# ActuatorController.net
KiCad netlist of a schematic drawn in EAGLE
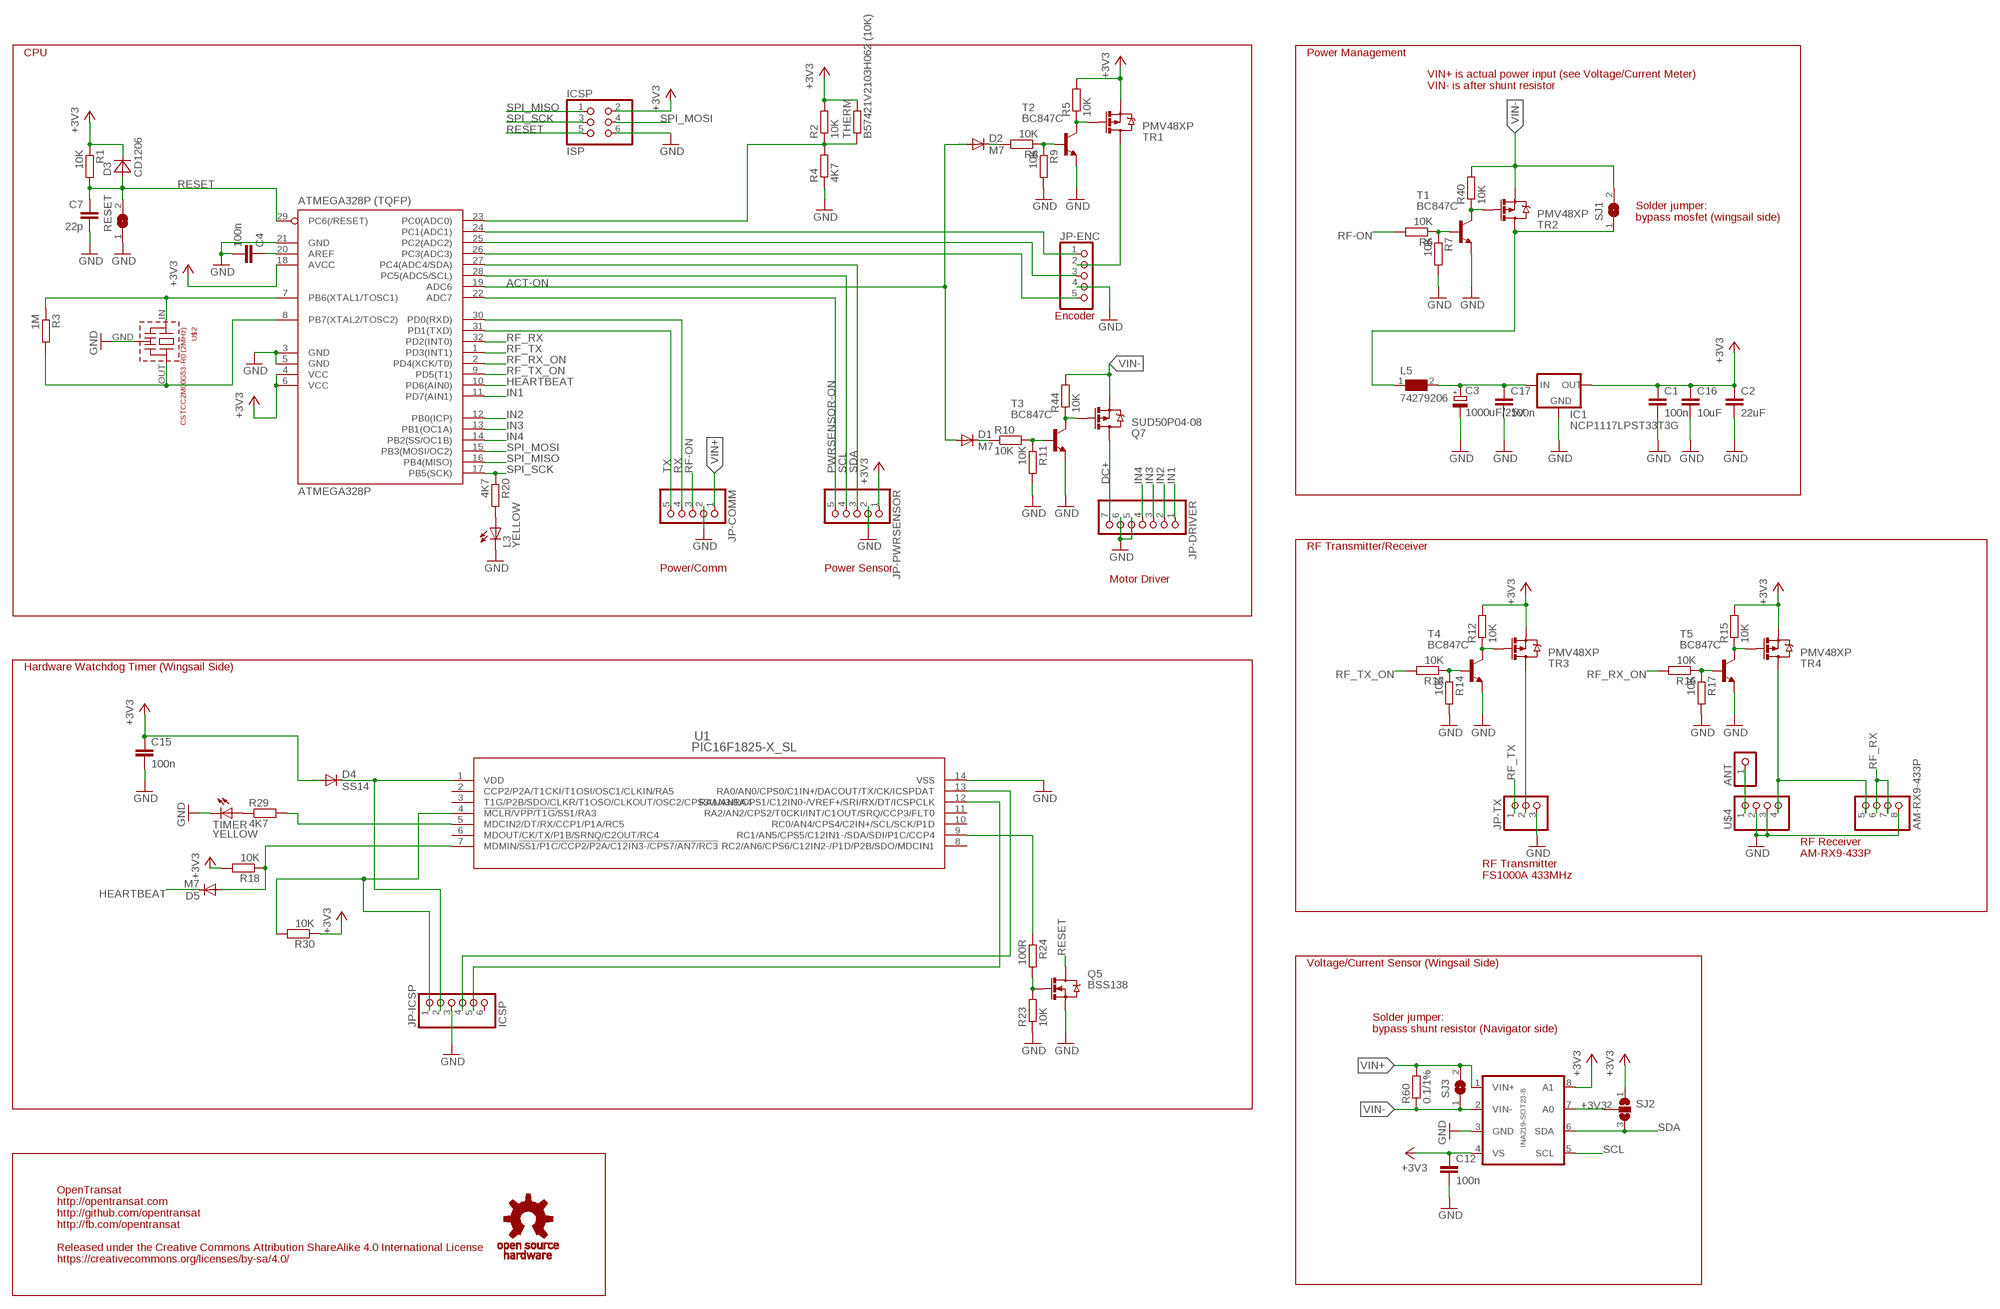
[diagram p0: schematic, sheet 1]

(export (version "E")
  (design (tool "Eeschema 10.0.6"))
  (components
    (comp (ref "ANT")
      (value "PINHD-1X1")
      (footprint "eagle-import:1X01")
      (libsource (lib "eagle-import") (part "PINHD-1X1"))
    )
    (comp (ref "ATMEGA328P")
      (value "ATMEGA328P (TQFP)")
      (footprint "eagle-import:TQFP32-08")
      (fields (field (name "MPN") "ATMEGA8-16AU"))
      (libsource (lib "eagle-import") (part "MEGA8-AI"))
    )
    (comp (ref "C1")
      (value "100n")
      (footprint "eagle-import:C0603")
      (libsource (lib "eagle-import") (part "C-EUC0603"))
    )
    (comp (ref "C2")
      (value "22uF")
      (footprint "eagle-import:C1210")
      (libsource (lib "eagle-import") (part "C-EUC1210"))
    )
    (comp (ref "C3")
      (value "1000uF/25V")
      (footprint "eagle-import:E5-10,5")
      (libsource (lib "eagle-import") (part "CPOL-EUE5-10.5"))
    )
    (comp (ref "C4")
      (value "100n")
      (footprint "eagle-import:C0603")
      (libsource (lib "eagle-import") (part "C-EUC0603"))
    )
    (comp (ref "C7")
      (value "22p")
      (footprint "eagle-import:C0603")
      (libsource (lib "eagle-import") (part "C-EUC0603"))
    )
    (comp (ref "C12")
      (value "100n")
      (footprint "eagle-import:C0603")
      (libsource (lib "eagle-import") (part "C-EUC0603"))
    )
    (comp (ref "C15")
      (value "100n")
      (footprint "eagle-import:C0603")
      (libsource (lib "eagle-import") (part "C-EUC0603"))
    )
    (comp (ref "C16")
      (value "10uF")
      (footprint "eagle-import:C1206")
      (libsource (lib "eagle-import") (part "C-EUC1206"))
    )
    (comp (ref "C17")
      (value "100n")
      (footprint "eagle-import:C0603")
      (libsource (lib "eagle-import") (part "C-EUC0603"))
    )
    (comp (ref "D1")
      (value "M7")
      (footprint "eagle-import:DO-214AC")
      (libsource (lib "eagle-import") (part "DIODE-DO-214AC"))
    )
    (comp (ref "D2")
      (value "M7")
      (footprint "eagle-import:DO-214AC")
      (libsource (lib "eagle-import") (part "DIODE-DO-214AC"))
    )
    (comp (ref "D3")
      (value "CD1206")
      (footprint "eagle-import:R1206")
      (libsource (lib "eagle-import") (part "CD1206"))
    )
    (comp (ref "D4")
      (value "SS14")
      (footprint "eagle-import:DO214AC")
      (libsource (lib "eagle-import") (part "DIODE-DO214AC"))
    )
    (comp (ref "D5")
      (value "M7")
      (footprint "eagle-import:DO-214AC")
      (libsource (lib "eagle-import") (part "DIODE-DO-214AC"))
    )
    (comp (ref "IC1")
      (value "NCP1117LPST33T3G")
      (footprint "eagle-import:SOT223")
      (fields (field (name "MF") "Texas Instruments") (field (name "MPN") "LM1117MP-3.3"))
      (libsource (lib "eagle-import") (part "LM1117?-MP3.3"))
    )
    (comp (ref "ICSP")
      (value "ISP")
      (footprint "eagle-import:2X03")
      (libsource (lib "eagle-import") (part "PINHD-2X3"))
    )
    (comp (ref "JP-COMM")
      (value "PINHD-1X5/90")
      (footprint "eagle-import:1X05_90")
      (libsource (lib "eagle-import") (part "PINHD-1X5/90"))
    )
    (comp (ref "JP-DRIVER")
      (value "PINHD-1X7/90")
      (footprint "eagle-import:1X07_90")
      (libsource (lib "eagle-import") (part "PINHD-1X7/90"))
    )
    (comp (ref "JP-ENC")
      (value "PINHD-1X5/90")
      (footprint "eagle-import:1X05_90")
      (libsource (lib "eagle-import") (part "PINHD-1X5/90"))
    )
    (comp (ref "JP-ICSP")
      (value "ICSP")
      (footprint "eagle-import:1X06")
      (libsource (lib "eagle-import") (part "PINHD-1X6"))
    )
    (comp (ref "JP-PWRSENSOR")
      (value "PINHD-1X5/90")
      (footprint "eagle-import:1X05_90")
      (libsource (lib "eagle-import") (part "PINHD-1X5/90"))
    )
    (comp (ref "JP-TX")
      (value "PINHD-1X3")
      (footprint "eagle-import:1X03")
      (libsource (lib "eagle-import") (part "PINHD-1X3"))
    )
    (comp (ref "L3")
      (value "YELLOW")
      (footprint "eagle-import:CHIPLED_0805")
      (libsource (lib "eagle-import") (part "LEDCHIPLED_0805"))
    )
    (comp (ref "L5")
      (value "74279206")
      (footprint "eagle-import:0805")
      (libsource (lib "eagle-import") (part "WE-CBF_0805"))
    )
    (comp (ref "Q5")
      (value "BSS138")
      (footprint "eagle-import:SOT23-3")
      (libsource (lib "eagle-import") (part "MOSFET-NCHANNEL_SOT23-3"))
    )
    (comp (ref "Q7")
      (value "SUD50P04-08")
      (footprint "eagle-import:D-PAK_TO252AA")
      (libsource (lib "eagle-import") (part "MOSFET-PCHANNEL_D-PAK"))
    )
    (comp (ref "R1")
      (value "10K")
      (footprint "eagle-import:R0603")
      (libsource (lib "eagle-import") (part "R-EU_R0603"))
    )
    (comp (ref "R2")
      (value "10K")
      (footprint "eagle-import:R0603")
      (libsource (lib "eagle-import") (part "R-EU_R0603"))
    )
    (comp (ref "R3")
      (value "1M")
      (footprint "eagle-import:R0603")
      (libsource (lib "eagle-import") (part "R-EU_R0603"))
    )
    (comp (ref "R4")
      (value "4K7")
      (footprint "eagle-import:R0603")
      (libsource (lib "eagle-import") (part "R-EU_R0603"))
    )
    (comp (ref "R5")
      (value "10K")
      (footprint "eagle-import:R0603")
      (libsource (lib "eagle-import") (part "R-EU_R0603"))
    )
    (comp (ref "R6")
      (value "10K")
      (footprint "eagle-import:R0603")
      (libsource (lib "eagle-import") (part "R-EU_R0603"))
    )
    (comp (ref "R7")
      (value "10K")
      (footprint "eagle-import:R0603")
      (libsource (lib "eagle-import") (part "R-EU_R0603"))
    )
    (comp (ref "R8")
      (value "10K")
      (footprint "eagle-import:R0603")
      (libsource (lib "eagle-import") (part "R-EU_R0603"))
    )
    (comp (ref "R9")
      (value "10K")
      (footprint "eagle-import:R0603")
      (libsource (lib "eagle-import") (part "R-EU_R0603"))
    )
    (comp (ref "R10")
      (value "10K")
      (footprint "eagle-import:R0603")
      (libsource (lib "eagle-import") (part "R-EU_R0603"))
    )
    (comp (ref "R11")
      (value "10K")
      (footprint "eagle-import:R0603")
      (libsource (lib "eagle-import") (part "R-EU_R0603"))
    )
    (comp (ref "R12")
      (value "10K")
      (footprint "eagle-import:R0603")
      (libsource (lib "eagle-import") (part "R-EU_R0603"))
    )
    (comp (ref "R13")
      (value "10K")
      (footprint "eagle-import:R0603")
      (libsource (lib "eagle-import") (part "R-EU_R0603"))
    )
    (comp (ref "R14")
      (value "10K")
      (footprint "eagle-import:R0603")
      (libsource (lib "eagle-import") (part "R-EU_R0603"))
    )
    (comp (ref "R15")
      (value "10K")
      (footprint "eagle-import:R0603")
      (libsource (lib "eagle-import") (part "R-EU_R0603"))
    )
    (comp (ref "R16")
      (value "10K")
      (footprint "eagle-import:R0603")
      (libsource (lib "eagle-import") (part "R-EU_R0603"))
    )
    (comp (ref "R17")
      (value "10K")
      (footprint "eagle-import:R0603")
      (libsource (lib "eagle-import") (part "R-EU_R0603"))
    )
    (comp (ref "R18")
      (value "10K")
      (footprint "eagle-import:R0603")
      (libsource (lib "eagle-import") (part "R-EU_R0603"))
    )
    (comp (ref "R20")
      (value "4K7")
      (footprint "eagle-import:R0603")
      (libsource (lib "eagle-import") (part "R-EU_R0603"))
    )
    (comp (ref "R23")
      (value "10K")
      (footprint "eagle-import:R0603")
      (libsource (lib "eagle-import") (part "R-EU_R0603"))
    )
    (comp (ref "R24")
      (value "100R")
      (footprint "eagle-import:R0603")
      (libsource (lib "eagle-import") (part "R-EU_R0603"))
    )
    (comp (ref "R29")
      (value "4K7")
      (footprint "eagle-import:R0603")
      (libsource (lib "eagle-import") (part "R-EU_R0603"))
    )
    (comp (ref "R30")
      (value "10K")
      (footprint "eagle-import:R0603")
      (libsource (lib "eagle-import") (part "R-EU_R0603"))
    )
    (comp (ref "R40")
      (value "10K")
      (footprint "eagle-import:R0603")
      (libsource (lib "eagle-import") (part "R-EU_R0603"))
    )
    (comp (ref "R44")
      (value "10K")
      (footprint "eagle-import:R0603")
      (libsource (lib "eagle-import") (part "R-EU_R0603"))
    )
    (comp (ref "R60")
      (value "0.1/1%")
      (footprint "eagle-import:R2512")
      (libsource (lib "eagle-import") (part "R-EU_R2512"))
    )
    (comp (ref "RESET")
      (value "SJW")
      (footprint "eagle-import:SJW")
      (libsource (lib "eagle-import") (part "SJW"))
    )
    (comp (ref "SJ1") (value "SJ") (footprint "eagle-import:SJ") (libsource (lib "eagle-import") (part "SJ")))
    (comp (ref "SJ2")
      (value "SJ2W")
      (footprint "eagle-import:SJ_2")
      (libsource (lib "eagle-import") (part "SJ2W"))
    )
    (comp (ref "SJ3") (value "SJ") (footprint "eagle-import:SJ") (libsource (lib "eagle-import") (part "SJ")))
    (comp (ref "T1")
      (value "BC847C")
      (footprint "eagle-import:SOT23")
      (libsource (lib "eagle-import") (part "BC847"))
    )
    (comp (ref "T2")
      (value "BC847C")
      (footprint "eagle-import:SOT23")
      (libsource (lib "eagle-import") (part "BC847"))
    )
    (comp (ref "T3")
      (value "BC847C")
      (footprint "eagle-import:SOT23")
      (libsource (lib "eagle-import") (part "BC847"))
    )
    (comp (ref "T4")
      (value "BC847C")
      (footprint "eagle-import:SOT23")
      (libsource (lib "eagle-import") (part "BC847"))
    )
    (comp (ref "T5")
      (value "BC847C")
      (footprint "eagle-import:SOT23")
      (libsource (lib "eagle-import") (part "BC847"))
    )
    (comp (ref "THERM")
      (value "B57421V2103H062 (10K)")
      (footprint "eagle-import:R0603")
      (libsource (lib "eagle-import") (part "R-EU_R0603"))
    )
    (comp (ref "TIMER")
      (value "YELLOW")
      (footprint "eagle-import:CHIPLED_0805")
      (libsource (lib "eagle-import") (part "LEDCHIPLED_0805"))
    )
    (comp (ref "TR1")
      (value "PMV48XP")
      (footprint "eagle-import:SOT23-3")
      (libsource (lib "eagle-import") (part "MOSFET-PCHANNEL_SOT23-3"))
    )
    (comp (ref "TR2")
      (value "PMV48XP")
      (footprint "eagle-import:SOT23-3")
      (libsource (lib "eagle-import") (part "MOSFET-PCHANNEL_SOT23-3"))
    )
    (comp (ref "TR3")
      (value "PMV48XP")
      (footprint "eagle-import:SOT23-3")
      (libsource (lib "eagle-import") (part "MOSFET-PCHANNEL_SOT23-3"))
    )
    (comp (ref "TR4")
      (value "PMV48XP")
      (footprint "eagle-import:SOT23-3")
      (libsource (lib "eagle-import") (part "MOSFET-PCHANNEL_SOT23-3"))
    )
    (comp (ref "U$1")
      (value "OSHW_S")
      (footprint "eagle-import:OSHWS")
      (libsource (lib "eagle-import") (part "OSHW_S"))
    )
    (comp (ref "U$2")
      (value "CSTCC2M00G53-R0 (2MHz)")
      (footprint "eagle-import:CSTCC")
      (libsource (lib "eagle-import") (part "CSTCC"))
    )
    (comp (ref "U$3")
      (value "INA219-SOT23-8")
      (footprint "eagle-import:SOT23-8")
      (libsource (lib "eagle-import") (part "INA219-SOT23-8"))
    )
    (comp (ref "U$4")
      (value "AM-RX9-433P")
      (footprint "eagle-import:1X04")
      (libsource (lib "eagle-import") (part "AM-RX9-433P"))
    )
    (comp (ref "U1")
      (value "PIC16F1825-X_SL")
      (footprint "eagle-import:SOIC14-N_MC")
      (libsource (lib "eagle-import") (part "PIC16F1825-X_SL"))
    )
  )
  (nets
    (net (code "1") (name "+3V3") (class "Default")
      (node (ref "ATMEGA328P") (pin "18") (pinfunction "AVCC_18") (pintype "power_in"))
      (node (ref "ATMEGA328P") (pin "4") (pinfunction "VCC_4") (pintype "power_in"))
      (node (ref "ATMEGA328P") (pin "6") (pinfunction "VCC_6") (pintype "power_in"))
      (node (ref "C1") (pin "1") (pinfunction "1_1") (pintype "passive"))
      (node (ref "C12") (pin "1") (pinfunction "1_1") (pintype "passive"))
      (node (ref "C15") (pin "1") (pinfunction "1_1") (pintype "passive"))
      (node (ref "C16") (pin "1") (pinfunction "1_1") (pintype "passive"))
      (node (ref "C2") (pin "1") (pinfunction "1_1") (pintype "passive"))
      (node (ref "D3") (pin "2") (pinfunction "C_2") (pintype "passive"))
      (node (ref "D4") (pin "A") (pinfunction "A_A") (pintype "passive"))
      (node (ref "IC1") (pin "2") (pinfunction "OUT_2") (pintype "passive"))
      (node (ref "IC1") (pin "4") (pinfunction "OUT_4") (pintype "passive"))
      (node (ref "ICSP") (pin "2") (pinfunction "2_2") (pintype "passive"))
      (node (ref "JP-PWRSENSOR") (pin "1") (pinfunction "1_1") (pintype "passive"))
      (node (ref "R1") (pin "1") (pinfunction "1_1") (pintype "passive"))
      (node (ref "R12") (pin "2") (pinfunction "2_2") (pintype "passive"))
      (node (ref "R15") (pin "2") (pinfunction "2_2") (pintype "passive"))
      (node (ref "R18") (pin "2") (pinfunction "2_2") (pintype "passive"))
      (node (ref "R2") (pin "2") (pinfunction "2_2") (pintype "passive"))
      (node (ref "R30") (pin "1") (pinfunction "1_1") (pintype "passive"))
      (node (ref "R5") (pin "2") (pinfunction "2_2") (pintype "passive"))
      (node (ref "SJ2") (pin "1") (pinfunction "1_1") (pintype "passive"))
      (node (ref "SJ2") (pin "2") (pinfunction "2_2") (pintype "passive"))
      (node (ref "THERM") (pin "2") (pinfunction "2_2") (pintype "passive"))
      (node (ref "TR1") (pin "2") (pinfunction "S_2") (pintype "passive"))
      (node (ref "TR3") (pin "2") (pinfunction "S_2") (pintype "passive"))
      (node (ref "TR4") (pin "2") (pinfunction "S_2") (pintype "passive"))
      (node (ref "U$3") (pin "4") (pinfunction "VS_4") (pintype "power_in"))
      (node (ref "U$3") (pin "7") (pinfunction "A0_7") (pintype "input"))
      (node (ref "U$3") (pin "8") (pinfunction "A1_8") (pintype "input"))
    )
    (net (code "2") (name "/ACT-ON") (class "Default")
      (node (ref "ATMEGA328P") (pin "19") (pinfunction "ADC6_19") (pintype "bidirectional"))
      (node (ref "D1") (pin "A") (pinfunction "A_A") (pintype "passive"))
      (node (ref "D2") (pin "A") (pinfunction "A_A") (pintype "passive"))
    )
    (net (code "3") (name "/DC+") (class "Default")
      (node (ref "JP-DRIVER") (pin "7") (pinfunction "7_7") (pintype "passive"))
      (node (ref "Q7") (pin "2") (pinfunction "D_2") (pintype "passive"))
    )
    (net (code "4") (name "/HEARTBEAT") (class "Default")
      (node (ref "ATMEGA328P") (pin "10") (pinfunction "PD6(AIN0)_10") (pintype "bidirectional"))
      (node (ref "D5") (pin "C") (pinfunction "C_C") (pintype "passive"))
    )
    (net (code "5") (name "/IN1") (class "Default")
      (node (ref "ATMEGA328P") (pin "11") (pinfunction "PD7(AIN1)_11") (pintype "bidirectional"))
      (node (ref "JP-DRIVER") (pin "1") (pinfunction "1_1") (pintype "passive"))
    )
    (net (code "6") (name "/IN2") (class "Default")
      (node (ref "ATMEGA328P") (pin "12") (pinfunction "PB0(ICP)_12") (pintype "bidirectional"))
      (node (ref "JP-DRIVER") (pin "2") (pinfunction "2_2") (pintype "passive"))
    )
    (net (code "7") (name "/IN3") (class "Default")
      (node (ref "ATMEGA328P") (pin "13") (pinfunction "PB1(OC1A)_13") (pintype "bidirectional"))
      (node (ref "JP-DRIVER") (pin "3") (pinfunction "3_3") (pintype "passive"))
    )
    (net (code "8") (name "/IN4") (class "Default")
      (node (ref "ATMEGA328P") (pin "14") (pinfunction "PB2(SS/OC1B)_14") (pintype "bidirectional"))
      (node (ref "JP-DRIVER") (pin "4") (pinfunction "4_4") (pintype "passive"))
    )
    (net (code "9") (name "/PWRSENSOR-ON") (class "Default")
      (node (ref "ATMEGA328P") (pin "22") (pinfunction "ADC7_22") (pintype "bidirectional"))
      (node (ref "JP-PWRSENSOR") (pin "5") (pinfunction "5_5") (pintype "passive"))
    )
    (net (code "10") (name "/RESET") (class "Default")
      (node (ref "ATMEGA328P") (pin "29") (pinfunction "PC6(/RESET)_29") (pintype "bidirectional"))
      (node (ref "C7") (pin "1") (pinfunction "1_1") (pintype "passive"))
      (node (ref "D3") (pin "1") (pinfunction "A_1") (pintype "passive"))
      (node (ref "ICSP") (pin "5") (pinfunction "5_5") (pintype "passive"))
      (node (ref "Q5") (pin "3") (pinfunction "D_3") (pintype "passive"))
      (node (ref "R1") (pin "2") (pinfunction "2_2") (pintype "passive"))
      (node (ref "RESET") (pin "2") (pinfunction "2_2") (pintype "passive"))
    )
    (net (code "11") (name "/RF-ON") (class "Default")
      (node (ref "JP-COMM") (pin "3") (pinfunction "3_3") (pintype "passive"))
      (node (ref "R6") (pin "2") (pinfunction "2_2") (pintype "passive"))
    )
    (net (code "12") (name "/RF_RX") (class "Default")
      (node (ref "ATMEGA328P") (pin "32") (pinfunction "PD2(INT0)_32") (pintype "bidirectional"))
      (node (ref "U$4") (pin "6") (pinfunction "6_6") (pintype "passive"))
      (node (ref "U$4") (pin "7") (pinfunction "7_7") (pintype "passive"))
    )
    (net (code "13") (name "/RF_RX_ON") (class "Default")
      (node (ref "ATMEGA328P") (pin "2") (pinfunction "PD4(XCK/T0)_2") (pintype "bidirectional"))
      (node (ref "R16") (pin "2") (pinfunction "2_2") (pintype "passive"))
    )
    (net (code "14") (name "/RF_TX") (class "Default")
      (node (ref "ATMEGA328P") (pin "1") (pinfunction "PD3(INT1)_1") (pintype "bidirectional"))
      (node (ref "JP-TX") (pin "1") (pinfunction "1_1") (pintype "passive"))
    )
    (net (code "15") (name "/RF_TX_ON") (class "Default")
      (node (ref "ATMEGA328P") (pin "9") (pinfunction "PD5(T1)_9") (pintype "bidirectional"))
      (node (ref "R13") (pin "2") (pinfunction "2_2") (pintype "passive"))
    )
    (net (code "16") (name "/RX") (class "Default")
      (node (ref "ATMEGA328P") (pin "30") (pinfunction "PD0(RXD)_30") (pintype "bidirectional"))
      (node (ref "JP-COMM") (pin "4") (pinfunction "4_4") (pintype "passive"))
    )
    (net (code "17") (name "/SCL") (class "Default")
      (node (ref "ATMEGA328P") (pin "28") (pinfunction "PC5(ADC5/SCL)_28") (pintype "bidirectional"))
      (node (ref "JP-PWRSENSOR") (pin "4") (pinfunction "4_4") (pintype "passive"))
      (node (ref "U$3") (pin "5") (pinfunction "SCL_5") (pintype "bidirectional"))
    )
    (net (code "18") (name "/SDA") (class "Default")
      (node (ref "ATMEGA328P") (pin "27") (pinfunction "PC4(ADC4/SDA)_27") (pintype "bidirectional"))
      (node (ref "JP-PWRSENSOR") (pin "3") (pinfunction "3_3") (pintype "passive"))
      (node (ref "SJ2") (pin "3") (pinfunction "3_3") (pintype "passive"))
      (node (ref "U$3") (pin "6") (pinfunction "SDA_6") (pintype "bidirectional"))
    )
    (net (code "19") (name "/SPI_MISO") (class "Default")
      (node (ref "ATMEGA328P") (pin "16") (pinfunction "PB4(MISO)_16") (pintype "bidirectional"))
      (node (ref "ICSP") (pin "1") (pinfunction "1_1") (pintype "passive"))
    )
    (net (code "20") (name "/SPI_MOSI") (class "Default")
      (node (ref "ATMEGA328P") (pin "15") (pinfunction "PB3(MOSI/OC2)_15") (pintype "bidirectional"))
      (node (ref "ICSP") (pin "4") (pinfunction "4_4") (pintype "passive"))
    )
    (net (code "21") (name "/SPI_SCK") (class "Default")
      (node (ref "ATMEGA328P") (pin "17") (pinfunction "PB5(SCK)_17") (pintype "bidirectional"))
      (node (ref "ICSP") (pin "3") (pinfunction "3_3") (pintype "passive"))
      (node (ref "R20") (pin "1") (pinfunction "1_1") (pintype "passive"))
    )
    (net (code "22") (name "/TX") (class "Default")
      (node (ref "ATMEGA328P") (pin "31") (pinfunction "PD1(TXD)_31") (pintype "bidirectional"))
      (node (ref "JP-COMM") (pin "5") (pinfunction "5_5") (pintype "passive"))
    )
    (net (code "23") (name "GND") (class "Default")
      (node (ref "ATMEGA328P") (pin "21") (pinfunction "GND_21") (pintype "power_in"))
      (node (ref "ATMEGA328P") (pin "3") (pinfunction "GND_3") (pintype "power_in"))
      (node (ref "ATMEGA328P") (pin "5") (pinfunction "GND_5") (pintype "power_in"))
      (node (ref "C1") (pin "2") (pinfunction "2_2") (pintype "passive"))
      (node (ref "C12") (pin "2") (pinfunction "2_2") (pintype "passive"))
      (node (ref "C15") (pin "2") (pinfunction "2_2") (pintype "passive"))
      (node (ref "C16") (pin "2") (pinfunction "2_2") (pintype "passive"))
      (node (ref "C17") (pin "2") (pinfunction "2_2") (pintype "passive"))
      (node (ref "C2") (pin "2") (pinfunction "2_2") (pintype "passive"))
      (node (ref "C3") (pin "-") (pinfunction "-_-") (pintype "passive"))
      (node (ref "C4") (pin "2") (pinfunction "2_2") (pintype "passive"))
      (node (ref "C7") (pin "2") (pinfunction "2_2") (pintype "passive"))
      (node (ref "IC1") (pin "1") (pinfunction "GND_1") (pintype "input"))
      (node (ref "ICSP") (pin "6") (pinfunction "6_6") (pintype "passive"))
      (node (ref "JP-COMM") (pin "2") (pinfunction "2_2") (pintype "passive"))
      (node (ref "JP-DRIVER") (pin "5") (pinfunction "5_5") (pintype "passive"))
      (node (ref "JP-DRIVER") (pin "6") (pinfunction "6_6") (pintype "passive"))
      (node (ref "JP-ENC") (pin "4") (pinfunction "4_4") (pintype "passive"))
      (node (ref "JP-ICSP") (pin "3") (pinfunction "3_3") (pintype "passive"))
      (node (ref "JP-PWRSENSOR") (pin "2") (pinfunction "2_2") (pintype "passive"))
      (node (ref "JP-TX") (pin "3") (pinfunction "3_3") (pintype "passive"))
      (node (ref "L3") (pin "C") (pinfunction "C_C") (pintype "passive"))
      (node (ref "Q5") (pin "2") (pinfunction "S_2") (pintype "passive"))
      (node (ref "R11") (pin "2") (pinfunction "2_2") (pintype "passive"))
      (node (ref "R14") (pin "2") (pinfunction "2_2") (pintype "passive"))
      (node (ref "R17") (pin "2") (pinfunction "2_2") (pintype "passive"))
      (node (ref "R23") (pin "1") (pinfunction "1_1") (pintype "passive"))
      (node (ref "R4") (pin "1") (pinfunction "1_1") (pintype "passive"))
      (node (ref "R7") (pin "2") (pinfunction "2_2") (pintype "passive"))
      (node (ref "R9") (pin "2") (pinfunction "2_2") (pintype "passive"))
      (node (ref "RESET") (pin "1") (pinfunction "1_1") (pintype "passive"))
      (node (ref "T1") (pin "2") (pinfunction "E_2") (pintype "passive"))
      (node (ref "T2") (pin "2") (pinfunction "E_2") (pintype "passive"))
      (node (ref "T3") (pin "2") (pinfunction "E_2") (pintype "passive"))
      (node (ref "T4") (pin "2") (pinfunction "E_2") (pintype "passive"))
      (node (ref "T5") (pin "2") (pinfunction "E_2") (pintype "passive"))
      (node (ref "TIMER") (pin "C") (pinfunction "C_C") (pintype "passive"))
      (node (ref "U$2") (pin "GND") (pinfunction "GND_GND") (pintype "power_in"))
      (node (ref "U$3") (pin "3") (pinfunction "GND_3") (pintype "power_in"))
      (node (ref "U$4") (pin "2") (pinfunction "2_2") (pintype "passive"))
      (node (ref "U$4") (pin "3") (pinfunction "3_3") (pintype "passive"))
      (node (ref "U$4") (pin "8") (pinfunction "8_8") (pintype "passive"))
      (node (ref "U1") (pin "14") (pinfunction "VSS_14") (pintype "power_in"))
    )
    (net (code "24") (name "Net-(ANT-Pad1)") (class "Default")
      (node (ref "ANT") (pin "1") (pinfunction "1_1") (pintype "passive"))
      (node (ref "U$4") (pin "1") (pinfunction "1_1") (pintype "passive"))
    )
    (net (code "25") (name "Net-(ATMEGA328P-AREF)") (class "Default")
      (node (ref "ATMEGA328P") (pin "20") (pinfunction "AREF_20") (pintype "passive"))
      (node (ref "C4") (pin "1") (pinfunction "1_1") (pintype "passive"))
    )
    (net (code "26") (name "Net-(ATMEGA328P-PB6(XTAL1{slash}TOSC1))") (class "Default")
      (node (ref "ATMEGA328P") (pin "7") (pinfunction "PB6(XTAL1/TOSC1)_7") (pintype "bidirectional"))
      (node (ref "R3") (pin "1") (pinfunction "1_1") (pintype "passive"))
      (node (ref "U$2") (pin "IN") (pinfunction "IN_IN") (pintype "input"))
    )
    (net (code "27") (name "Net-(ATMEGA328P-PB7(XTAL2{slash}TOSC2))") (class "Default")
      (node (ref "ATMEGA328P") (pin "8") (pinfunction "PB7(XTAL2/TOSC2)_8") (pintype "bidirectional"))
      (node (ref "R3") (pin "2") (pinfunction "2_2") (pintype "passive"))
      (node (ref "U$2") (pin "OUT") (pinfunction "OUT_OUT") (pintype "output"))
    )
    (net (code "28") (name "Net-(ATMEGA328P-PC0(ADC0))") (class "Default")
      (node (ref "ATMEGA328P") (pin "23") (pinfunction "PC0(ADC0)_23") (pintype "bidirectional"))
      (node (ref "R2") (pin "1") (pinfunction "1_1") (pintype "passive"))
      (node (ref "R4") (pin "2") (pinfunction "2_2") (pintype "passive"))
      (node (ref "THERM") (pin "1") (pinfunction "1_1") (pintype "passive"))
    )
    (net (code "29") (name "Net-(ATMEGA328P-PC1(ADC1))") (class "Default")
      (node (ref "ATMEGA328P") (pin "24") (pinfunction "PC1(ADC1)_24") (pintype "bidirectional"))
      (node (ref "JP-ENC") (pin "1") (pinfunction "1_1") (pintype "passive"))
    )
    (net (code "30") (name "Net-(ATMEGA328P-PC2(ADC2))") (class "Default")
      (node (ref "ATMEGA328P") (pin "25") (pinfunction "PC2(ADC2)_25") (pintype "bidirectional"))
      (node (ref "JP-ENC") (pin "3") (pinfunction "3_3") (pintype "passive"))
    )
    (net (code "31") (name "Net-(ATMEGA328P-PC3(ADC3))") (class "Default")
      (node (ref "ATMEGA328P") (pin "26") (pinfunction "PC3(ADC3)_26") (pintype "bidirectional"))
      (node (ref "JP-ENC") (pin "5") (pinfunction "5_5") (pintype "passive"))
    )
    (net (code "32") (name "Net-(D1-PadC)") (class "Default")
      (node (ref "D1") (pin "C") (pinfunction "C_C") (pintype "passive"))
      (node (ref "R10") (pin "1") (pinfunction "1_1") (pintype "passive"))
    )
    (net (code "33") (name "Net-(D2-PadC)") (class "Default")
      (node (ref "D2") (pin "C") (pinfunction "C_C") (pintype "passive"))
      (node (ref "R8") (pin "2") (pinfunction "2_2") (pintype "passive"))
    )
    (net (code "34") (name "Net-(IC1-IN)") (class "Default")
      (node (ref "C17") (pin "1") (pinfunction "1_1") (pintype "passive"))
      (node (ref "C3") (pin "+") (pinfunction "+_+") (pintype "passive"))
      (node (ref "IC1") (pin "3") (pinfunction "IN_3") (pintype "input"))
      (node (ref "L5") (pin "2") (pinfunction "2_2") (pintype "passive"))
    )
    (net (code "35") (name "Net-(L3-PadA)") (class "Default")
      (node (ref "L3") (pin "A") (pinfunction "A_A") (pintype "passive"))
      (node (ref "R20") (pin "2") (pinfunction "2_2") (pintype "passive"))
    )
    (net (code "36") (name "Net-(Q5-G)") (class "Default")
      (node (ref "Q5") (pin "1") (pinfunction "G_1") (pintype "passive"))
      (node (ref "R23") (pin "2") (pinfunction "2_2") (pintype "passive"))
      (node (ref "R24") (pin "2") (pinfunction "2_2") (pintype "passive"))
    )
    (net (code "37") (name "Net-(Q7-G)") (class "Default")
      (node (ref "Q7") (pin "1") (pinfunction "G_1") (pintype "passive"))
      (node (ref "R44") (pin "1") (pinfunction "1_1") (pintype "passive"))
      (node (ref "T3") (pin "3") (pinfunction "C_3") (pintype "passive"))
    )
    (net (code "38") (name "Net-(R29-Pad1)") (class "Default")
      (node (ref "R29") (pin "1") (pinfunction "1_1") (pintype "passive"))
      (node (ref "TIMER") (pin "A") (pinfunction "A_A") (pintype "passive"))
    )
    (net (code "39") (name "Net-(T1-B)") (class "Default")
      (node (ref "R6") (pin "1") (pinfunction "1_1") (pintype "passive"))
      (node (ref "R7") (pin "1") (pinfunction "1_1") (pintype "passive"))
      (node (ref "T1") (pin "1") (pinfunction "B_1") (pintype "passive"))
    )
    (net (code "40") (name "Net-(T1-C)") (class "Default")
      (node (ref "R40") (pin "1") (pinfunction "1_1") (pintype "passive"))
      (node (ref "T1") (pin "3") (pinfunction "C_3") (pintype "passive"))
      (node (ref "TR2") (pin "1") (pinfunction "G_1") (pintype "passive"))
    )
    (net (code "41") (name "Net-(T2-B)") (class "Default")
      (node (ref "R8") (pin "1") (pinfunction "1_1") (pintype "passive"))
      (node (ref "R9") (pin "1") (pinfunction "1_1") (pintype "passive"))
      (node (ref "T2") (pin "1") (pinfunction "B_1") (pintype "passive"))
    )
    (net (code "42") (name "Net-(T2-C)") (class "Default")
      (node (ref "R5") (pin "1") (pinfunction "1_1") (pintype "passive"))
      (node (ref "T2") (pin "3") (pinfunction "C_3") (pintype "passive"))
      (node (ref "TR1") (pin "1") (pinfunction "G_1") (pintype "passive"))
    )
    (net (code "43") (name "Net-(T3-B)") (class "Default")
      (node (ref "R10") (pin "2") (pinfunction "2_2") (pintype "passive"))
      (node (ref "R11") (pin "1") (pinfunction "1_1") (pintype "passive"))
      (node (ref "T3") (pin "1") (pinfunction "B_1") (pintype "passive"))
    )
    (net (code "44") (name "Net-(T4-B)") (class "Default")
      (node (ref "R13") (pin "1") (pinfunction "1_1") (pintype "passive"))
      (node (ref "R14") (pin "1") (pinfunction "1_1") (pintype "passive"))
      (node (ref "T4") (pin "1") (pinfunction "B_1") (pintype "passive"))
    )
    (net (code "45") (name "Net-(T4-C)") (class "Default")
      (node (ref "R12") (pin "1") (pinfunction "1_1") (pintype "passive"))
      (node (ref "T4") (pin "3") (pinfunction "C_3") (pintype "passive"))
      (node (ref "TR3") (pin "1") (pinfunction "G_1") (pintype "passive"))
    )
    (net (code "46") (name "Net-(T5-B)") (class "Default")
      (node (ref "R16") (pin "1") (pinfunction "1_1") (pintype "passive"))
      (node (ref "R17") (pin "1") (pinfunction "1_1") (pintype "passive"))
      (node (ref "T5") (pin "1") (pinfunction "B_1") (pintype "passive"))
    )
    (net (code "47") (name "Net-(T5-C)") (class "Default")
      (node (ref "R15") (pin "1") (pinfunction "1_1") (pintype "passive"))
      (node (ref "T5") (pin "3") (pinfunction "C_3") (pintype "passive"))
      (node (ref "TR4") (pin "1") (pinfunction "G_1") (pintype "passive"))
    )
    (net (code "48") (name "Net-(TR1-D)") (class "Default")
      (node (ref "JP-ENC") (pin "2") (pinfunction "2_2") (pintype "passive"))
      (node (ref "TR1") (pin "3") (pinfunction "D_3") (pintype "passive"))
    )
    (net (code "49") (name "Net-(TR2-D)") (class "Default")
      (node (ref "L5") (pin "1") (pinfunction "1_1") (pintype "passive"))
      (node (ref "SJ1") (pin "1") (pinfunction "1_1") (pintype "passive"))
      (node (ref "TR2") (pin "3") (pinfunction "D_3") (pintype "passive"))
    )
    (net (code "50") (name "Net-(TR3-D)") (class "Default")
      (node (ref "JP-TX") (pin "2") (pinfunction "2_2") (pintype "passive"))
      (node (ref "TR3") (pin "3") (pinfunction "D_3") (pintype "passive"))
    )
    (net (code "51") (name "Net-(TR4-D)") (class "Default")
      (node (ref "TR4") (pin "3") (pinfunction "D_3") (pintype "passive"))
      (node (ref "U$4") (pin "4") (pinfunction "4_4") (pintype "passive"))
      (node (ref "U$4") (pin "5") (pinfunction "5_5") (pintype "passive"))
    )
    (net (code "52") (name "Net-(U1-MDCIN2{slash}DT{slash}RX{slash}CCP1{slash}P1A{slash}RC5)") (class "Default")
      (node (ref "R29") (pin "2") (pinfunction "2_2") (pintype "passive"))
      (node (ref "U1") (pin "5") (pinfunction "MDCIN2/DT/RX/CCP1/P1A/RC5_5") (pintype "bidirectional"))
    )
    (net (code "53") (name "Net-(U1-MDMIN{slash}~{SS1{slash}P1C{slash}CCP2{slash}P2A{slash}C12IN3-{slash}CPS7{slash}AN7{slash}RC3})") (class "Default")
      (node (ref "D5") (pin "A") (pinfunction "A_A") (pintype "passive"))
      (node (ref "R18") (pin "1") (pinfunction "1_1") (pintype "passive"))
      (node (ref "U1") (pin "7") (pinfunction "MDMIN/~{SS1/P1C/CCP2/P2A/C12IN3-/CPS7/AN7/RC3}_7") (pintype "bidirectional"))
    )
    (net (code "54") (name "Net-(U1-RA0{slash}AN0{slash}CPS0{slash}C1IN+{slash}DACOUT{slash}TX{slash}CK{slash}ICSPDAT)") (class "Default")
      (node (ref "JP-ICSP") (pin "4") (pinfunction "4_4") (pintype "passive"))
      (node (ref "U1") (pin "13") (pinfunction "RA0/AN0/CPS0/C1IN+/DACOUT/TX/CK/ICSPDAT_13") (pintype "bidirectional"))
    )
    (net (code "55") (name "Net-(U1-RA1{slash}AN1{slash}CPS1{slash}C12IN0-{slash}VREF+{slash}SRI{slash}RX{slash}DT{slash}ICSPCLK)") (class "Default")
      (node (ref "JP-ICSP") (pin "5") (pinfunction "5_5") (pintype "passive"))
      (node (ref "U1") (pin "12") (pinfunction "RA1/AN1/CPS1/C12IN0-/VREF+/SRI/RX/DT/ICSPCLK_12") (pintype "bidirectional"))
    )
    (net (code "56") (name "Net-(U1-RC1{slash}AN5{slash}CPS5{slash}C12IN1-{slash}SDA{slash}SDI{slash}P1C{slash}CCP4)") (class "Default")
      (node (ref "R24") (pin "1") (pinfunction "1_1") (pintype "passive"))
      (node (ref "U1") (pin "9") (pinfunction "RC1/AN5/CPS5/C12IN1-/SDA/SDI/P1C/CCP4_9") (pintype "bidirectional"))
    )
    (net (code "57") (name "Net-(U1-VDD)") (class "Default")
      (node (ref "D4") (pin "C") (pinfunction "C_C") (pintype "passive"))
      (node (ref "JP-ICSP") (pin "2") (pinfunction "2_2") (pintype "passive"))
      (node (ref "U1") (pin "1") (pinfunction "VDD_1") (pintype "power_in"))
    )
    (net (code "58") (name "Net-(U1-~{MCLR{slash}VPP{slash}T1G{slash}}SS1{slash}RA3)") (class "Default")
      (node (ref "JP-ICSP") (pin "1") (pinfunction "1_1") (pintype "passive"))
      (node (ref "R30") (pin "2") (pinfunction "2_2") (pintype "passive"))
      (node (ref "U1") (pin "4") (pinfunction "~{MCLR/VPP/T1G/}SS1/RA3_4") (pintype "bidirectional"))
    )
    (net (code "59") (name "VIN+") (class "Default")
      (node (ref "JP-COMM") (pin "1") (pinfunction "1_1") (pintype "passive"))
      (node (ref "R60") (pin "2") (pinfunction "2_2") (pintype "passive"))
      (node (ref "SJ3") (pin "2") (pinfunction "2_2") (pintype "passive"))
      (node (ref "U$3") (pin "1") (pinfunction "VIN+_1") (pintype "input"))
    )
    (net (code "60") (name "VIN-") (class "Default")
      (node (ref "Q7") (pin "3") (pinfunction "S_3") (pintype "passive"))
      (node (ref "R40") (pin "2") (pinfunction "2_2") (pintype "passive"))
      (node (ref "R44") (pin "2") (pinfunction "2_2") (pintype "passive"))
      (node (ref "R60") (pin "1") (pinfunction "1_1") (pintype "passive"))
      (node (ref "SJ1") (pin "2") (pinfunction "2_2") (pintype "passive"))
      (node (ref "SJ3") (pin "1") (pinfunction "1_1") (pintype "passive"))
      (node (ref "TR2") (pin "2") (pinfunction "S_2") (pintype "passive"))
      (node (ref "U$3") (pin "2") (pinfunction "VIN-_2") (pintype "input"))
    )
    (net (code "61") (name "unconnected-(JP-ICSP-Pad6)") (class "Default")
      (node (ref "JP-ICSP") (pin "6") (pinfunction "6_6") (pintype "passive"))
    )
    (net (code "62") (name "unconnected-(U1-CCP2{slash}P2A{slash}T1CKI{slash}T1OSI{slash}OSC1{slash}CLKIN{slash}RA5-Pad2)") (class "Default")
      (node (ref "U1") (pin "2") (pinfunction "CCP2/P2A/T1CKI/T1OSI/OSC1/CLKIN/RA5_2") (pintype "bidirectional"))
    )
    (net (code "63") (name "unconnected-(U1-MDOUT{slash}CK{slash}TX{slash}P1B{slash}SRNQ{slash}C2OUT{slash}RC4-Pad6)") (class "Default")
      (node (ref "U1") (pin "6") (pinfunction "MDOUT/CK/TX/P1B/SRNQ/C2OUT/RC4_6") (pintype "bidirectional"))
    )
    (net (code "64") (name "unconnected-(U1-RA2{slash}AN2{slash}CPS2{slash}T0CKI{slash}INT{slash}C1OUT{slash}SRQ{slash}CCP3{slash}FLT0-Pad11)") (class "Default")
      (node (ref "U1") (pin "11") (pinfunction "RA2/AN2/CPS2/T0CKI/INT/C1OUT/SRQ/CCP3/FLT0_11") (pintype "bidirectional"))
    )
    (net (code "65") (name "unconnected-(U1-RC0{slash}AN4{slash}CPS4{slash}C2IN+{slash}SCL{slash}SCK{slash}P1D-Pad10)") (class "Default")
      (node (ref "U1") (pin "10") (pinfunction "RC0/AN4/CPS4/C2IN+/SCL/SCK/P1D_10") (pintype "bidirectional"))
    )
    (net (code "66") (name "unconnected-(U1-RC2{slash}AN6{slash}CPS6{slash}C12IN2-{slash}P1D{slash}P2B{slash}SDO{slash}MDCIN1-Pad8)") (class "Default")
      (node (ref "U1") (pin "8") (pinfunction "RC2/AN6/CPS6/C12IN2-/P1D/P2B/SDO/MDCIN1_8") (pintype "bidirectional"))
    )
    (net (code "67") (name "unconnected-(U1-T1G{slash}P2B{slash}SDO{slash}CLKR{slash}T1OSO{slash}CLKOUT{slash}OSC2{slash}CPS3{slash}AN3{slash}RA4-Pad3)") (class "Default")
      (node (ref "U1") (pin "3") (pinfunction "T1G/P2B/SDO/CLKR/T1OSO/CLKOUT/OSC2/CPS3/AN3/RA4_3") (pintype "bidirectional"))
    )
  )
)
